# boost-board.net
KiCad netlist of a schematic drawn in EAGLE
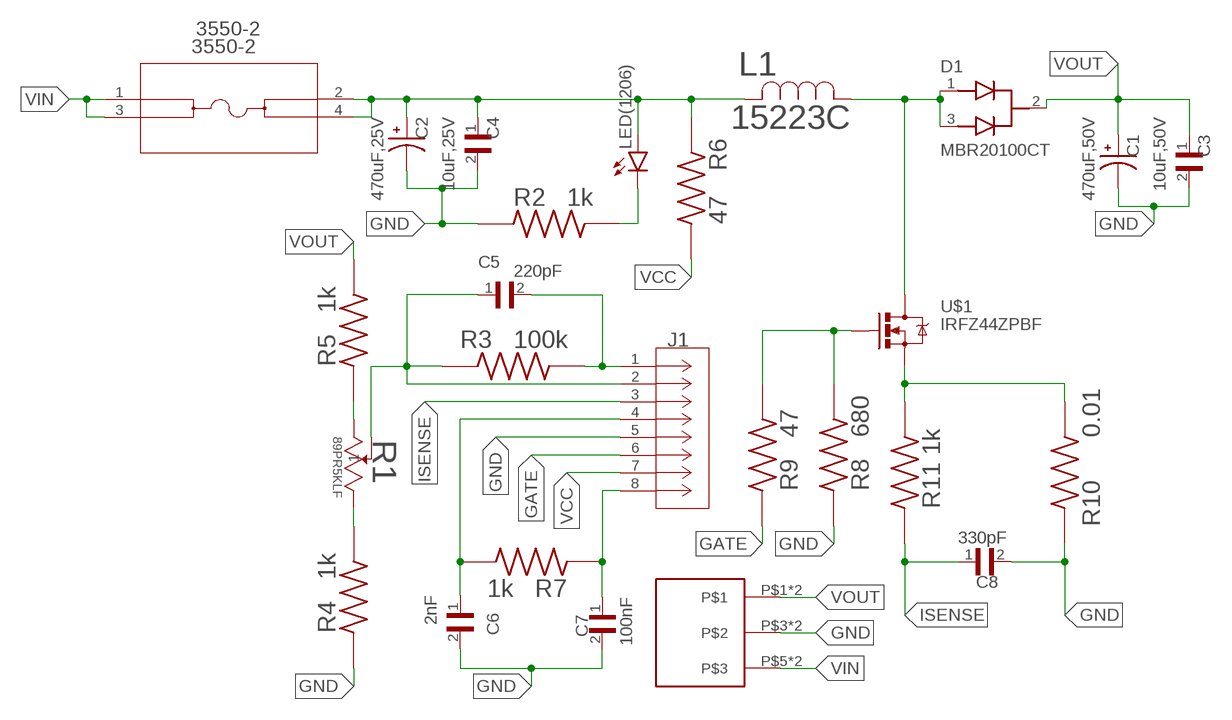
[diagram p0: schematic, sheet 1]

(export (version "E")
  (design (tool "Eeschema 10.0.6"))
  (components
    (comp (ref "3550-2")
      (value "3550-2")
      (footprint "eagle-import:3550-2_KEY")
      (fields (field (name "COPYRIGHT") "Copyright (C) 2018 Accelerated Designs. All rights reserved"))
      (libsource (lib "eagle-import") (part "3550-2"))
    )
    (comp (ref "C1")
      (value "470uF,50V")
      (footprint "eagle-import:CAPPRD500W60D1250H2200")
      (fields (field (name "MF") "Rubycon") (field (name "MP") "50YXG470MEFC12.5X20"))
      (libsource (lib "eagle-import") (part "50YXG470MEFC12.5X20"))
    )
    (comp (ref "C2")
      (value "470uF,25V")
      (footprint "eagle-import:CAPPRD500W60D1000H1800")
      (fields (field (name "MF") "Rubycon") (field (name "MP") "25YXG470MEFCT810X16"))
      (libsource (lib "eagle-import") (part "25YXG470MEFCT810X16"))
    )
    (comp (ref "C3")
      (value "10uF,50V")
      (footprint "eagle-import:CAPC3216X88N")
      (fields
        (field (name "DIGI-KEY_PART_NUMBER") "399-7357-2-ND")
        (field (name "MF") "KEMET")
        (field (name "MP") "C1206C104K5RAC7210")
      )
      (libsource (lib "eagle-import") (part "C1206C104K5RAC7210"))
    )
    (comp (ref "C4")
      (value "10uF,25V")
      (footprint "eagle-import:CAPC3216X88N")
      (fields
        (field (name "DIGI-KEY_PART_NUMBER") "399-7357-2-ND")
        (field (name "MF") "KEMET")
        (field (name "MP") "C1206C104K5RAC7210")
      )
      (libsource (lib "eagle-import") (part "C1206C104K5RAC7210"))
    )
    (comp (ref "C5")
      (value "220pF")
      (footprint "eagle-import:CAPC3216X88N")
      (fields
        (field (name "DIGI-KEY_PART_NUMBER") "399-7357-2-ND")
        (field (name "MF") "KEMET")
        (field (name "MP") "C1206C104K5RAC7210")
      )
      (libsource (lib "eagle-import") (part "C1206C104K5RAC7210"))
    )
    (comp (ref "C6")
      (value "2nF")
      (footprint "eagle-import:CAPC3216X88N")
      (fields
        (field (name "DIGI-KEY_PART_NUMBER") "399-7357-2-ND")
        (field (name "MF") "KEMET")
        (field (name "MP") "C1206C104K5RAC7210")
      )
      (libsource (lib "eagle-import") (part "C1206C104K5RAC7210"))
    )
    (comp (ref "C7")
      (value "100nF")
      (footprint "eagle-import:CAPC3216X88N")
      (fields
        (field (name "DIGI-KEY_PART_NUMBER") "399-7357-2-ND")
        (field (name "MF") "KEMET")
        (field (name "MP") "C1206C104K5RAC7210")
      )
      (libsource (lib "eagle-import") (part "C1206C104K5RAC7210"))
    )
    (comp (ref "C8")
      (value "330pF")
      (footprint "eagle-import:CAPC3216X88N")
      (fields
        (field (name "DIGI-KEY_PART_NUMBER") "399-7357-2-ND")
        (field (name "MF") "KEMET")
        (field (name "MP") "C1206C104K5RAC7210")
      )
      (libsource (lib "eagle-import") (part "C1206C104K5RAC7210"))
    )
    (comp (ref "D1")
      (value "MBR20100CT")
      (footprint "eagle-import:TO254P1066X482X2286-3")
      (fields (field (name "MF") "Motorola"))
      (libsource (lib "eagle-import") (part "MBR20100CT"))
    )
    (comp (ref "J1")
      (value "DILB8P-223TLF")
      (footprint "eagle-import:CONN_DILB8P-223TLF_AMP")
      (fields (field (name "COPYRIGHT") "Copyright (C) 2018 Accelerated Designs. All rights reserved"))
      (libsource (lib "eagle-import") (part "DILB8P-223TLF"))
    )
    (comp (ref "L1")
      (value "15223C")
      (footprint "eagle-import:15223C_MUR")
      (libsource (lib "eagle-import") (part "15223C"))
    )
    (comp (ref "LED(1206)")
      (value "LED-FKIT-1206")
      (footprint "eagle-import:FKIT-LED-1206")
      (libsource (lib "eagle-import") (part "LED-FKIT-1206"))
    )
    (comp (ref "R1")
      (value "89PR5KLF")
      (footprint "eagle-import:RES3_89P_TTE")
      (fields (field (name "COPYRIGHT") "Copyright (C) 2016 Accelerated Designs. All rights reserved"))
      (libsource (lib "eagle-import") (part "89PR5KLF"))
    )
    (comp (ref "R2")
      (value "1k")
      (footprint "eagle-import:RESC3216X70N")
      (fields
        (field (name "DIGI-KEY_PART_NUMBER") "RMCF1206JT1K00CT-ND")
        (field (name "MF") "Stackpole Electronics Inc")
        (field (name "MP") "RMCF1206JT1K00")
      )
      (libsource (lib "eagle-import") (part "RMCF1206JT1K00"))
    )
    (comp (ref "R3")
      (value "100k")
      (footprint "eagle-import:RESC3216X70N")
      (fields
        (field (name "DIGI-KEY_PART_NUMBER") "RMCF1206JT1K00CT-ND")
        (field (name "MF") "Stackpole Electronics Inc")
        (field (name "MP") "RMCF1206JT1K00")
      )
      (libsource (lib "eagle-import") (part "RMCF1206JT1K00"))
    )
    (comp (ref "R4")
      (value "1k")
      (footprint "eagle-import:RESC3216X70N")
      (fields
        (field (name "DIGI-KEY_PART_NUMBER") "RMCF1206JT1K00CT-ND")
        (field (name "MF") "Stackpole Electronics Inc")
        (field (name "MP") "RMCF1206JT1K00")
      )
      (libsource (lib "eagle-import") (part "RMCF1206JT1K00"))
    )
    (comp (ref "R5")
      (value "1k")
      (footprint "eagle-import:RESC3216X70N")
      (fields
        (field (name "DIGI-KEY_PART_NUMBER") "RMCF1206JT1K00CT-ND")
        (field (name "MF") "Stackpole Electronics Inc")
        (field (name "MP") "RMCF1206JT1K00")
      )
      (libsource (lib "eagle-import") (part "RMCF1206JT1K00"))
    )
    (comp (ref "R6")
      (value "47")
      (footprint "eagle-import:RESC3216X70N")
      (fields
        (field (name "DIGI-KEY_PART_NUMBER") "RMCF1206JT1K00CT-ND")
        (field (name "MF") "Stackpole Electronics Inc")
        (field (name "MP") "RMCF1206JT1K00")
      )
      (libsource (lib "eagle-import") (part "RMCF1206JT1K00"))
    )
    (comp (ref "R7")
      (value "1k")
      (footprint "eagle-import:RESC3216X70N")
      (fields
        (field (name "DIGI-KEY_PART_NUMBER") "RMCF1206JT1K00CT-ND")
        (field (name "MF") "Stackpole Electronics Inc")
        (field (name "MP") "RMCF1206JT1K00")
      )
      (libsource (lib "eagle-import") (part "RMCF1206JT1K00"))
    )
    (comp (ref "R8")
      (value "680")
      (footprint "eagle-import:RESC3216X70N")
      (fields
        (field (name "DIGI-KEY_PART_NUMBER") "RMCF1206JT1K00CT-ND")
        (field (name "MF") "Stackpole Electronics Inc")
        (field (name "MP") "RMCF1206JT1K00")
      )
      (libsource (lib "eagle-import") (part "RMCF1206JT1K00"))
    )
    (comp (ref "R9")
      (value "47")
      (footprint "eagle-import:RESC3216X70N")
      (fields
        (field (name "DIGI-KEY_PART_NUMBER") "RMCF1206JT1K00CT-ND")
        (field (name "MF") "Stackpole Electronics Inc")
        (field (name "MP") "RMCF1206JT1K00")
      )
      (libsource (lib "eagle-import") (part "RMCF1206JT1K00"))
    )
    (comp (ref "R10")
      (value "0.01")
      (footprint "eagle-import:RESC3216X70N")
      (fields
        (field (name "DIGI-KEY_PART_NUMBER") "RMCF1206JT1K00CT-ND")
        (field (name "MF") "Stackpole Electronics Inc")
        (field (name "MP") "RMCF1206JT1K00")
      )
      (libsource (lib "eagle-import") (part "RMCF1206JT1K00"))
    )
    (comp (ref "R11")
      (value "1k")
      (footprint "eagle-import:RESC3216X70N")
      (fields
        (field (name "DIGI-KEY_PART_NUMBER") "RMCF1206JT1K00CT-ND")
        (field (name "MF") "Stackpole Electronics Inc")
        (field (name "MP") "RMCF1206JT1K00")
      )
      (libsource (lib "eagle-import") (part "RMCF1206JT1K00"))
    )
    (comp (ref "U$1")
      (value "IRFZ44ZPBF")
      (footprint "eagle-import:TO-220")
      (fields
        (field (name "DIGI-KEY_PART_NUMBER") "IRFZ44ZPBF-ND")
        (field (name "MF") "Infineon Technologies")
      )
      (libsource (lib "eagle-import") (part "IRFZ44ZPBF"))
    )
    (comp (ref "U$2")
      (value "FX30B-3S-3.81DSA")
      (footprint "eagle-import:FX30B-4S-3.81DSA")
      (libsource (lib "eagle-import") (part "FX30B-3S-3.81DSA"))
    )
  )
  (nets
    (net (code "1") (name "GATE") (class "Default")
      (node (ref "J1") (pin "6") (pinfunction "6_6") (pintype "passive"))
      (node (ref "R9") (pin "1") (pinfunction "1_1") (pintype "passive"))
    )
    (net (code "2") (name "GND") (class "Default")
      (node (ref "C1") (pin "N") (pinfunction "N_N") (pintype "passive"))
      (node (ref "C2") (pin "N") (pinfunction "N_N") (pintype "passive"))
      (node (ref "C3") (pin "2") (pinfunction "2_2") (pintype "passive"))
      (node (ref "C4") (pin "2") (pinfunction "2_2") (pintype "passive"))
      (node (ref "C6") (pin "2") (pinfunction "2_2") (pintype "passive"))
      (node (ref "C7") (pin "2") (pinfunction "2_2") (pintype "passive"))
      (node (ref "C8") (pin "2") (pinfunction "2_2") (pintype "passive"))
      (node (ref "J1") (pin "5") (pinfunction "5_5") (pintype "passive"))
      (node (ref "R10") (pin "1") (pinfunction "1_1") (pintype "passive"))
      (node (ref "R2") (pin "1") (pinfunction "1_1") (pintype "passive"))
      (node (ref "R4") (pin "1") (pinfunction "1_1") (pintype "passive"))
      (node (ref "R8") (pin "1") (pinfunction "1_1") (pintype "passive"))
      (node (ref "U$2") (pin "P$3") (pinfunction "P$2_P$3") (pintype "bidirectional"))
      (node (ref "U$2") (pin "P$4") (pinfunction "P$2_P$4") (pintype "bidirectional"))
    )
    (net (code "3") (name "ISENSE") (class "Default")
      (node (ref "C8") (pin "1") (pinfunction "1_1") (pintype "passive"))
      (node (ref "J1") (pin "3") (pinfunction "3_3") (pintype "passive"))
      (node (ref "R11") (pin "1") (pinfunction "1_1") (pintype "passive"))
    )
    (net (code "4") (name "Net-(3550-2-Pad2)") (class "Default")
      (node (ref "3550-2") (pin "2") (pinfunction "2_2") (pintype "passive"))
      (node (ref "3550-2") (pin "4") (pinfunction "4_4") (pintype "passive"))
      (node (ref "C2") (pin "P") (pinfunction "P_P") (pintype "passive"))
      (node (ref "C4") (pin "1") (pinfunction "1_1") (pintype "passive"))
      (node (ref "L1") (pin "2") (pinfunction "2_2") (pintype "passive"))
      (node (ref "LED(1206)") (pin "A") (pinfunction "A_A") (pintype "passive"))
      (node (ref "R6") (pin "2") (pinfunction "2_2") (pintype "passive"))
    )
    (net (code "5") (name "Net-(C5-Pad1)") (class "Default")
      (node (ref "C5") (pin "1") (pinfunction "1_1") (pintype "passive"))
      (node (ref "J1") (pin "2") (pinfunction "2_2") (pintype "passive"))
      (node (ref "R1") (pin "2") (pinfunction "2_2") (pintype "passive"))
      (node (ref "R3") (pin "1") (pinfunction "1_1") (pintype "passive"))
    )
    (net (code "6") (name "Net-(C5-Pad2)") (class "Default")
      (node (ref "C5") (pin "2") (pinfunction "2_2") (pintype "passive"))
      (node (ref "J1") (pin "1") (pinfunction "1_1") (pintype "passive"))
      (node (ref "R3") (pin "2") (pinfunction "2_2") (pintype "passive"))
    )
    (net (code "7") (name "Net-(C6-Pad1)") (class "Default")
      (node (ref "C6") (pin "1") (pinfunction "1_1") (pintype "passive"))
      (node (ref "J1") (pin "4") (pinfunction "4_4") (pintype "passive"))
      (node (ref "R7") (pin "2") (pinfunction "2_2") (pintype "passive"))
    )
    (net (code "8") (name "Net-(C7-Pad1)") (class "Default")
      (node (ref "C7") (pin "1") (pinfunction "1_1") (pintype "passive"))
      (node (ref "J1") (pin "8") (pinfunction "8_8") (pintype "passive"))
      (node (ref "R7") (pin "1") (pinfunction "1_1") (pintype "passive"))
    )
    (net (code "9") (name "Net-(D1-ANODE1)") (class "Default")
      (node (ref "D1") (pin "1") (pinfunction "ANODE1_1") (pintype "passive"))
      (node (ref "D1") (pin "3") (pinfunction "ANODE2_3") (pintype "passive"))
      (node (ref "L1") (pin "1") (pinfunction "1_1") (pintype "passive"))
      (node (ref "U$1") (pin "2") (pinfunction "D_2") (pintype "passive"))
    )
    (net (code "10") (name "Net-(LED(1206)-PadC)") (class "Default")
      (node (ref "LED(1206)") (pin "C") (pinfunction "C_C") (pintype "passive"))
      (node (ref "R2") (pin "2") (pinfunction "2_2") (pintype "passive"))
    )
    (net (code "11") (name "Net-(R1-1)") (class "Default")
      (node (ref "R1") (pin "3") (pinfunction "1_3") (pintype "passive"))
      (node (ref "R5") (pin "1") (pinfunction "1_1") (pintype "passive"))
    )
    (net (code "12") (name "Net-(R1-3)") (class "Default")
      (node (ref "R1") (pin "1") (pinfunction "3_1") (pintype "passive"))
      (node (ref "R4") (pin "2") (pinfunction "2_2") (pintype "passive"))
    )
    (net (code "13") (name "Net-(U$1-G)") (class "Default")
      (node (ref "R8") (pin "2") (pinfunction "2_2") (pintype "passive"))
      (node (ref "R9") (pin "2") (pinfunction "2_2") (pintype "passive"))
      (node (ref "U$1") (pin "1") (pinfunction "G_1") (pintype "passive"))
    )
    (net (code "14") (name "Net-(U$1-S)") (class "Default")
      (node (ref "R10") (pin "2") (pinfunction "2_2") (pintype "passive"))
      (node (ref "R11") (pin "2") (pinfunction "2_2") (pintype "passive"))
      (node (ref "U$1") (pin "3") (pinfunction "S_3") (pintype "passive"))
    )
    (net (code "15") (name "VCC") (class "Default")
      (node (ref "J1") (pin "7") (pinfunction "7_7") (pintype "passive"))
      (node (ref "R6") (pin "1") (pinfunction "1_1") (pintype "passive"))
    )
    (net (code "16") (name "VIN") (class "Default")
      (node (ref "3550-2") (pin "1") (pinfunction "1_1") (pintype "passive"))
      (node (ref "3550-2") (pin "3") (pinfunction "3_3") (pintype "passive"))
      (node (ref "U$2") (pin "P$5") (pinfunction "P$3_P$5") (pintype "bidirectional"))
      (node (ref "U$2") (pin "P$6") (pinfunction "P$3_P$6") (pintype "bidirectional"))
    )
    (net (code "17") (name "VOUT") (class "Default")
      (node (ref "C1") (pin "P") (pinfunction "P_P") (pintype "passive"))
      (node (ref "C3") (pin "1") (pinfunction "1_1") (pintype "passive"))
      (node (ref "D1") (pin "2") (pinfunction "COMMON_CATHODE_2") (pintype "passive"))
      (node (ref "R5") (pin "2") (pinfunction "2_2") (pintype "passive"))
      (node (ref "U$2") (pin "P$1") (pinfunction "P$1_P$1") (pintype "bidirectional"))
      (node (ref "U$2") (pin "P$2") (pinfunction "P$1_P$2") (pintype "bidirectional"))
    )
  )
)
